# 08_SAMA7G54-PMIC.net
KiCad netlist of a schematic drawn in Altium Designer
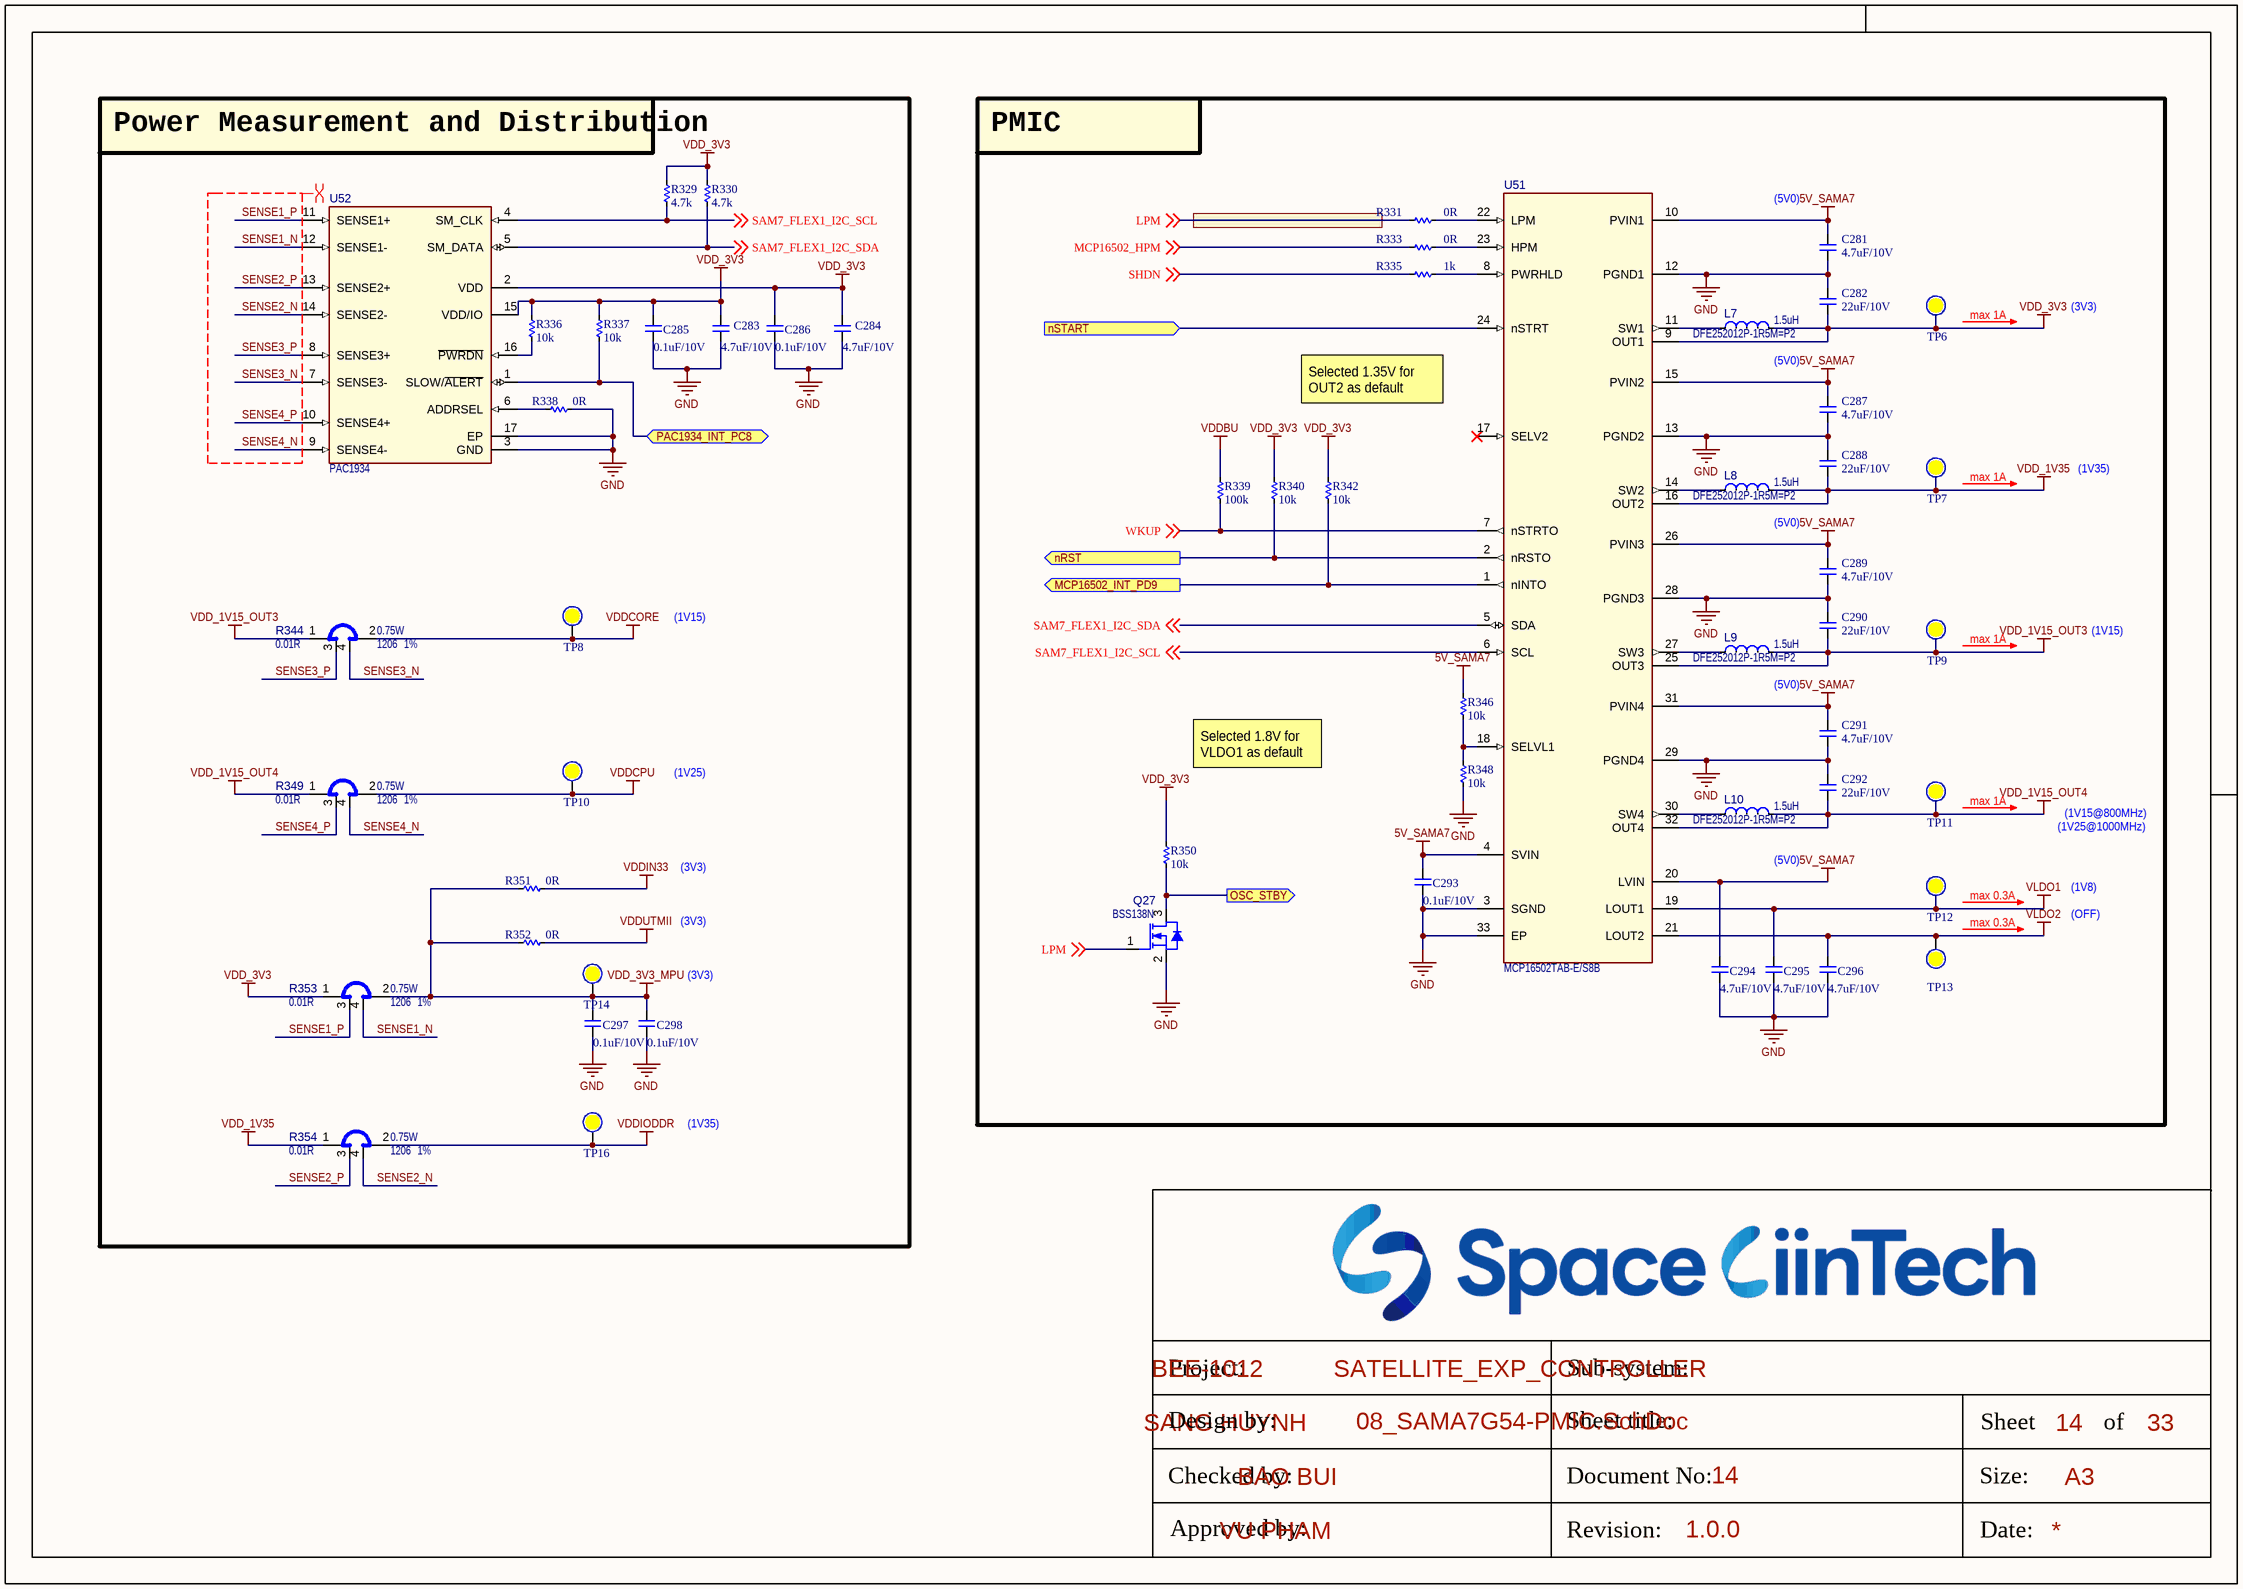
[diagram p0: 08_SAMA7G54-PMIC.SchDoc]

(export (version "E")
  (design (tool "Eeschema 10.0.6"))
  (components
    (comp (ref "C281")
      (value "4.7uF/10V")
      (footprint "CAP_C_1005X50_L")
      (description "CAP")
      (libsource (lib "LABLIB") (part "_CAP_C_2"))
    )
    (comp (ref "C282")
      (value "22uF/10V")
      (footprint "CAP_C_1608X80")
      (description "CAP")
      (libsource (lib "LABLIB") (part "_CAP_C_2"))
    )
    (comp (ref "C283")
      (value "4.7uF/10V")
      (footprint "CAP_C_1005X50_L")
      (description "CAP")
      (libsource (lib "LABLIB") (part "_CAP_C_2"))
    )
    (comp (ref "C284")
      (value "4.7uF/10V")
      (footprint "CAP_C_1005X50_L")
      (description "CAP")
      (libsource (lib "LABLIB") (part "_CAP_C_2"))
    )
    (comp (ref "C285")
      (value "0.1uF/10V")
      (footprint "CAP_C_1005X50_L")
      (description "CAP")
      (libsource (lib "LABLIB") (part "_CAP_C_2"))
    )
    (comp (ref "C286")
      (value "0.1uF/10V")
      (footprint "CAP_C_0603x30")
      (description "CAP")
      (libsource (lib "LABLIB") (part "_CAP_C_2"))
    )
    (comp (ref "C287")
      (value "4.7uF/10V")
      (footprint "CAP_C_1005X50_L")
      (description "CAP")
      (libsource (lib "LABLIB") (part "_CAP_C_2"))
    )
    (comp (ref "C288")
      (value "22uF/10V")
      (footprint "CAP_C_1608X80")
      (description "CAP")
      (libsource (lib "LABLIB") (part "_CAP_C_2"))
    )
    (comp (ref "C289")
      (value "4.7uF/10V")
      (footprint "CAP_C_1005X50_L")
      (description "CAP")
      (libsource (lib "LABLIB") (part "_CAP_C_2"))
    )
    (comp (ref "C290")
      (value "22uF/10V")
      (footprint "CAP_C_1608X80")
      (description "CAP")
      (libsource (lib "LABLIB") (part "_CAP_C_2"))
    )
    (comp (ref "C291")
      (value "4.7uF/10V")
      (footprint "CAP_C_1005X50_L")
      (description "CAP")
      (libsource (lib "LABLIB") (part "_CAP_C_2"))
    )
    (comp (ref "C292")
      (value "22uF/10V")
      (footprint "CAP_C_1608X80")
      (description "CAP")
      (libsource (lib "LABLIB") (part "_CAP_C_2"))
    )
    (comp (ref "C293")
      (value "0.1uF/10V")
      (footprint "CAP_C_0603x30")
      (description "CAP")
      (libsource (lib "LABLIB") (part "_CAP_C_2"))
    )
    (comp (ref "C294")
      (value "4.7uF/10V")
      (footprint "CAP_C_1005X50_L")
      (description "CAP")
      (libsource (lib "LABLIB") (part "_CAP_C_2"))
    )
    (comp (ref "C295")
      (value "4.7uF/10V")
      (footprint "CAP_C_1005X50_L")
      (description "CAP")
      (libsource (lib "LABLIB") (part "_CAP_C_2"))
    )
    (comp (ref "C296")
      (value "4.7uF/10V")
      (footprint "CAP_C_1005X50_L")
      (description "CAP")
      (libsource (lib "LABLIB") (part "_CAP_C_2"))
    )
    (comp (ref "C297")
      (value "0.1uF/10V")
      (footprint "CAP_C_0603x30")
      (description "CAP")
      (libsource (lib "LABLIB") (part "_CAP_C_2"))
    )
    (comp (ref "C298")
      (value "0.1uF/10V")
      (footprint "CAP_C_0603x30")
      (description "CAP")
      (libsource (lib "LABLIB") (part "_CAP_C_2"))
    )
    (comp (ref "L7")
      (value "1.5uH")
      (footprint "IND_C_1008")
      (description "Inductor")
      (fields
        (field (name "MANUFACTURER PART NUMBER 1") "DFE252012P-1R5M=P2")
        (field (name "Comment") "DFE252012P-1R5M=P2")
        (field (name "OWNER") "Razvan Cristescu")
      )
      (libsource (lib "LABLIB") (part "Inductor"))
    )
    (comp (ref "L8")
      (value "1.5uH")
      (footprint "IND_C_1008")
      (description "Inductor")
      (fields
        (field (name "MANUFACTURER PART NUMBER 1") "DFE252012P-1R5M=P2")
        (field (name "Comment") "DFE252012P-1R5M=P2")
        (field (name "OWNER") "Razvan Cristescu")
      )
      (libsource (lib "LABLIB") (part "Inductor"))
    )
    (comp (ref "L9")
      (value "1.5uH")
      (footprint "IND_C_1008")
      (description "Inductor")
      (fields
        (field (name "MANUFACTURER PART NUMBER 1") "DFE252012P-1R5M=P2")
        (field (name "Comment") "DFE252012P-1R5M=P2")
        (field (name "OWNER") "Razvan Cristescu")
      )
      (libsource (lib "LABLIB") (part "Inductor"))
    )
    (comp (ref "L10")
      (value "1.5uH")
      (footprint "IND_C_1008")
      (description "Inductor")
      (fields
        (field (name "MANUFACTURER PART NUMBER 1") "DFE252012P-1R5M=P2")
        (field (name "Comment") "DFE252012P-1R5M=P2")
        (field (name "OWNER") "Razvan Cristescu")
      )
      (libsource (lib "LABLIB") (part "Inductor"))
    )
    (comp (ref "Q27")
      (value "BSS138N")
      (footprint "SOT-23-3")
      (description "Transistor MOS")
      (fields
        (field (name "POWER") "0.36W")
        (field (name "VOLTAGE") "60V")
        (field (name "OWNER") "Dragos Danaila")
      )
      (libsource (lib "LABLIB") (part "Transistor MOS-N GSD"))
    )
    (comp (ref "R329")
      (value "4.7k")
      (footprint "RES_C_1005x30_L")
      (description "RES")
      (libsource (lib "LABLIB") (part "_RES_B_2"))
    )
    (comp (ref "R330")
      (value "4.7k")
      (footprint "RES_C_1005x30_L")
      (description "RES")
      (libsource (lib "LABLIB") (part "_RES_B_2"))
    )
    (comp (ref "R331")
      (value "0R")
      (footprint "RES_C_0603X30")
      (description "RES")
      (libsource (lib "LABLIB") (part "_RES_B_2"))
    )
    (comp (ref "R333")
      (value "0R")
      (footprint "RES_C_0603X30")
      (description "RES")
      (libsource (lib "LABLIB") (part "_RES_B_2"))
    )
    (comp (ref "R335")
      (value "1k")
      (footprint "RES_C_0603X30")
      (description "RES")
      (libsource (lib "LABLIB") (part "_RES_B_2"))
    )
    (comp (ref "R336")
      (value "10k")
      (footprint "RES_C_1005x30_L")
      (description "RES")
      (libsource (lib "LABLIB") (part "_RES_B_2"))
    )
    (comp (ref "R337")
      (value "10k")
      (footprint "RES_C_1005x30_L")
      (description "RES")
      (libsource (lib "LABLIB") (part "_RES_B_2"))
    )
    (comp (ref "R338")
      (value "0R")
      (footprint "RES_C_0603X30")
      (description "RES")
      (libsource (lib "LABLIB") (part "_RES_B_2"))
    )
    (comp (ref "R339")
      (value "100k")
      (footprint "RES_C_0603X30")
      (description "RES")
      (libsource (lib "LABLIB") (part "_RES_B_2"))
    )
    (comp (ref "R340")
      (value "10k")
      (footprint "RES_C_0603X30")
      (description "RES")
      (libsource (lib "LABLIB") (part "_RES_B_2"))
    )
    (comp (ref "R342")
      (value "10k")
      (footprint "RES_C_0603X30")
      (description "RES")
      (libsource (lib "LABLIB") (part "_RES_B_2"))
    )
    (comp (ref "R344")
      (value "0.01R")
      (footprint "RES_C_1206_SHUNT")
      (description "Shunt")
      (fields
        (field (name "PACKAGE") "1206")
        (field (name "TOLERANCE") "1%")
        (field (name "POWER") "0.75W")
        (field (name "Comment") "KRL1632E-M-R010-F-T5")
        (field (name "OWNER") "Ciprian Abramov")
      )
      (libsource (lib "LABLIB") (part "Shunt 4 Pin"))
    )
    (comp (ref "R346")
      (value "10k")
      (footprint "RES_C_0603X30")
      (description "RES")
      (libsource (lib "LABLIB") (part "_RES_B_2"))
    )
    (comp (ref "R348")
      (value "10k")
      (footprint "RES_C_0603X30")
      (description "RES")
      (libsource (lib "LABLIB") (part "_RES_B_2"))
    )
    (comp (ref "R349")
      (value "0.01R")
      (footprint "RES_C_1206_SHUNT")
      (description "Shunt")
      (fields
        (field (name "PACKAGE") "1206")
        (field (name "TOLERANCE") "1%")
        (field (name "POWER") "0.75W")
        (field (name "Comment") "KRL1632E-M-R010-F-T5")
        (field (name "OWNER") "Ciprian Abramov")
      )
      (libsource (lib "LABLIB") (part "Shunt 4 Pin"))
    )
    (comp (ref "R350")
      (value "10k")
      (footprint "RES_C_0603X30")
      (description "RES")
      (libsource (lib "LABLIB") (part "_RES_B_2"))
    )
    (comp (ref "R351")
      (value "0R")
      (footprint "RES_C_1608X60_L")
      (description "RES")
      (libsource (lib "LABLIB") (part "_RES_B_2"))
    )
    (comp (ref "R352")
      (value "0R")
      (footprint "RES_C_1608X60_L")
      (description "RES")
      (libsource (lib "LABLIB") (part "_RES_B_2"))
    )
    (comp (ref "R353")
      (value "0.01R")
      (footprint "RES_C_1206_SHUNT")
      (description "Shunt")
      (fields
        (field (name "PACKAGE") "1206")
        (field (name "TOLERANCE") "1%")
        (field (name "POWER") "0.75W")
        (field (name "Comment") "KRL1632E-M-R010-F-T5")
        (field (name "OWNER") "Ciprian Abramov")
      )
      (libsource (lib "LABLIB") (part "Shunt 4 Pin"))
    )
    (comp (ref "R354")
      (value "0.01R")
      (footprint "RES_C_1206_SHUNT")
      (description "Shunt")
      (fields
        (field (name "PACKAGE") "1206")
        (field (name "TOLERANCE") "1%")
        (field (name "POWER") "0.75W")
        (field (name "Comment") "KRL1632E-M-R010-F-T5")
        (field (name "OWNER") "Ciprian Abramov")
      )
      (libsource (lib "LABLIB") (part "Shunt 4 Pin"))
    )
    (comp (ref "TP6")
      (value "~")
      (footprint "Testpoint_50")
      (description "Test Point")
      (libsource (lib "LABLIB") (part "Test Point"))
    )
    (comp (ref "TP7")
      (value "~")
      (footprint "Testpoint_50")
      (description "Test Point")
      (libsource (lib "LABLIB") (part "Test Point"))
    )
    (comp (ref "TP8")
      (value "~")
      (footprint "Testpoint_50")
      (description "Test Point")
      (libsource (lib "LABLIB") (part "Test Point"))
    )
    (comp (ref "TP9")
      (value "~")
      (footprint "Testpoint_50")
      (description "Test Point")
      (libsource (lib "LABLIB") (part "Test Point"))
    )
    (comp (ref "TP10")
      (value "~")
      (footprint "Testpoint_50")
      (description "Test Point")
      (libsource (lib "LABLIB") (part "Test Point"))
    )
    (comp (ref "TP11")
      (value "~")
      (footprint "Testpoint_50")
      (description "Test Point")
      (libsource (lib "LABLIB") (part "Test Point"))
    )
    (comp (ref "TP12")
      (value "~")
      (footprint "Testpoint_50")
      (description "Test Point")
      (libsource (lib "LABLIB") (part "Test Point"))
    )
    (comp (ref "TP13")
      (value "~")
      (footprint "Testpoint_50")
      (description "Test Point")
      (libsource (lib "") (part "Test Point_1"))
    )
    (comp (ref "TP14")
      (value "~")
      (footprint "Testpoint_50")
      (description "Test Point")
      (libsource (lib "LABLIB") (part "Test Point"))
    )
    (comp (ref "TP16")
      (value "~")
      (footprint "Testpoint_50")
      (description "Test Point")
      (libsource (lib "LABLIB") (part "Test Point"))
    )
    (comp (ref "U51")
      (value "MCP16502TAB-E/S8B")
      (footprint "QFN-32_5X5_EP3.7X3.7")
      (fields (field (name "Comment") "MCP16502 QFN-32") (field (name "OWNER") "Dragos Danaila"))
      (libsource (lib "LABLIB") (part "MCP16502 QFN-32"))
    )
    (comp (ref "U52")
      (value "PAC1934")
      (footprint "UQFN-16_4X4_EP2.6X2.6")
      (fields (field (name "Comment") "PAC1934 UQFN-16") (field (name "OWNER") "Ciprian Abramov"))
      (libsource (lib "LABLIB") (part "PAC1934 UQFN-16"))
    )
  )
  (nets
    (net (code "1") (name "/MCP16502_INT_PD9") (class "Default")
      (node (ref "R342") (pin "1") (pinfunction "1_1") (pintype "passive"))
      (node (ref "U51") (pin "1") (pinfunction "nINTO_1") (pintype "output"))
    )
    (net (code "2") (name "/OSC_STBY") (class "Default")
      (node (ref "Q27") (pin "3") (pinfunction "D_3") (pintype "passive"))
      (node (ref "R350") (pin "2") (pinfunction "2_2") (pintype "passive"))
    )
    (net (code "3") (name "/PAC1934_INT_PC8") (class "Default")
      (node (ref "R337") (pin "2") (pinfunction "2_2") (pintype "passive"))
      (node (ref "U52") (pin "1") (pinfunction "SLOW/~{ALERT}_1") (pintype "bidirectional"))
    )
    (net (code "4") (name "/SENSE1_N") (class "Default")
      (node (ref "R353") (pin "4") (pinfunction "4_4") (pintype "passive"))
      (node (ref "U52") (pin "12") (pinfunction "SENSE1-_12") (pintype "input"))
    )
    (net (code "5") (name "/SENSE1_P") (class "Default")
      (node (ref "R353") (pin "3") (pinfunction "3_3") (pintype "passive"))
      (node (ref "U52") (pin "11") (pinfunction "SENSE1+_11") (pintype "input"))
    )
    (net (code "6") (name "/SENSE2_N") (class "Default")
      (node (ref "R354") (pin "4") (pinfunction "4_4") (pintype "passive"))
      (node (ref "U52") (pin "14") (pinfunction "SENSE2-_14") (pintype "input"))
    )
    (net (code "7") (name "/SENSE2_P") (class "Default")
      (node (ref "R354") (pin "3") (pinfunction "3_3") (pintype "passive"))
      (node (ref "U52") (pin "13") (pinfunction "SENSE2+_13") (pintype "input"))
    )
    (net (code "8") (name "/SENSE3_N") (class "Default")
      (node (ref "R344") (pin "4") (pinfunction "4_4") (pintype "passive"))
      (node (ref "U52") (pin "7") (pinfunction "SENSE3-_7") (pintype "input"))
    )
    (net (code "9") (name "/SENSE3_P") (class "Default")
      (node (ref "R344") (pin "3") (pinfunction "3_3") (pintype "passive"))
      (node (ref "U52") (pin "8") (pinfunction "SENSE3+_8") (pintype "input"))
    )
    (net (code "10") (name "/SENSE4_N") (class "Default")
      (node (ref "R349") (pin "4") (pinfunction "4_4") (pintype "passive"))
      (node (ref "U52") (pin "9") (pinfunction "SENSE4-_9") (pintype "input"))
    )
    (net (code "11") (name "/SENSE4_P") (class "Default")
      (node (ref "R349") (pin "3") (pinfunction "3_3") (pintype "passive"))
      (node (ref "U52") (pin "10") (pinfunction "SENSE4+_10") (pintype "input"))
    )
    (net (code "12") (name "/nRST") (class "Default")
      (node (ref "R340") (pin "1") (pinfunction "1_1") (pintype "passive"))
      (node (ref "U51") (pin "2") (pinfunction "nRSTO_2") (pintype "output"))
    )
    (net (code "13") (name "/nSTART") (class "Default")
      (node (ref "U51") (pin "24") (pinfunction "nSTRT_24") (pintype "input"))
    )
    (net (code "14") (name "5V_SAMA7") (class "Default")
      (node (ref "C281") (pin "1") (pinfunction "1_1") (pintype "passive"))
      (node (ref "C287") (pin "1") (pinfunction "1_1") (pintype "passive"))
      (node (ref "C289") (pin "1") (pinfunction "1_1") (pintype "passive"))
      (node (ref "C291") (pin "1") (pinfunction "1_1") (pintype "passive"))
      (node (ref "C293") (pin "1") (pinfunction "1_1") (pintype "passive"))
      (node (ref "C294") (pin "1") (pinfunction "1_1") (pintype "passive"))
      (node (ref "R346") (pin "1") (pinfunction "1_1") (pintype "passive"))
      (node (ref "U51") (pin "10") (pinfunction "PVIN1_10") (pintype "power_in"))
      (node (ref "U51") (pin "15") (pinfunction "PVIN2_15") (pintype "power_in"))
      (node (ref "U51") (pin "20") (pinfunction "LVIN_20") (pintype "power_in"))
      (node (ref "U51") (pin "26") (pinfunction "PVIN3_26") (pintype "power_in"))
      (node (ref "U51") (pin "31") (pinfunction "PVIN4_31") (pintype "power_in"))
      (node (ref "U51") (pin "4") (pinfunction "SVIN_4") (pintype "power_in"))
    )
    (net (code "15") (name "GND") (class "Default")
      (node (ref "C281") (pin "2") (pinfunction "2_2") (pintype "passive"))
      (node (ref "C282") (pin "1") (pinfunction "1_1") (pintype "passive"))
      (node (ref "C283") (pin "2") (pinfunction "2_2") (pintype "passive"))
      (node (ref "C284") (pin "2") (pinfunction "2_2") (pintype "passive"))
      (node (ref "C285") (pin "2") (pinfunction "2_2") (pintype "passive"))
      (node (ref "C286") (pin "2") (pinfunction "2_2") (pintype "passive"))
      (node (ref "C287") (pin "2") (pinfunction "2_2") (pintype "passive"))
      (node (ref "C288") (pin "1") (pinfunction "1_1") (pintype "passive"))
      (node (ref "C289") (pin "2") (pinfunction "2_2") (pintype "passive"))
      (node (ref "C290") (pin "1") (pinfunction "1_1") (pintype "passive"))
      (node (ref "C291") (pin "2") (pinfunction "2_2") (pintype "passive"))
      (node (ref "C292") (pin "1") (pinfunction "1_1") (pintype "passive"))
      (node (ref "C293") (pin "2") (pinfunction "2_2") (pintype "passive"))
      (node (ref "C294") (pin "2") (pinfunction "2_2") (pintype "passive"))
      (node (ref "C295") (pin "2") (pinfunction "2_2") (pintype "passive"))
      (node (ref "C296") (pin "2") (pinfunction "2_2") (pintype "passive"))
      (node (ref "C297") (pin "2") (pinfunction "2_2") (pintype "passive"))
      (node (ref "C298") (pin "2") (pinfunction "2_2") (pintype "passive"))
      (node (ref "Q27") (pin "2") (pinfunction "S_2") (pintype "passive"))
      (node (ref "R338") (pin "2") (pinfunction "2_2") (pintype "passive"))
      (node (ref "R348") (pin "2") (pinfunction "2_2") (pintype "passive"))
      (node (ref "U51") (pin "12") (pinfunction "PGND1_12") (pintype "power_in"))
      (node (ref "U51") (pin "13") (pinfunction "PGND2_13") (pintype "power_in"))
      (node (ref "U51") (pin "28") (pinfunction "PGND3_28") (pintype "power_in"))
      (node (ref "U51") (pin "29") (pinfunction "PGND4_29") (pintype "power_in"))
      (node (ref "U51") (pin "3") (pinfunction "SGND_3") (pintype "power_in"))
      (node (ref "U51") (pin "33") (pinfunction "EP_33") (pintype "power_in"))
      (node (ref "U52") (pin "17") (pinfunction "EP_17") (pintype "passive"))
      (node (ref "U52") (pin "3") (pinfunction "GND_3") (pintype "power_in"))
    )
    (net (code "16") (name "LPM") (class "Default")
      (node (ref "Q27") (pin "1") (pinfunction "G_1") (pintype "passive"))
      (node (ref "R331") (pin "1") (pinfunction "1_1") (pintype "passive"))
    )
    (net (code "17") (name "MCP16502_HPM") (class "Default")
      (node (ref "R333") (pin "1") (pinfunction "1_1") (pintype "passive"))
    )
    (net (code "18") (name "Net-(L7-S)") (class "Default")
      (node (ref "L7") (pin "1") (pinfunction "S_1") (pintype "passive"))
      (node (ref "U51") (pin "11") (pinfunction "SW1_11") (pintype "output"))
    )
    (net (code "19") (name "Net-(L8-S)") (class "Default")
      (node (ref "L8") (pin "1") (pinfunction "S_1") (pintype "passive"))
      (node (ref "U51") (pin "14") (pinfunction "SW2_14") (pintype "output"))
    )
    (net (code "20") (name "Net-(L9-S)") (class "Default")
      (node (ref "L9") (pin "1") (pinfunction "S_1") (pintype "passive"))
      (node (ref "U51") (pin "27") (pinfunction "SW3_27") (pintype "output"))
    )
    (net (code "21") (name "Net-(L10-S)") (class "Default")
      (node (ref "L10") (pin "1") (pinfunction "S_1") (pintype "passive"))
      (node (ref "U51") (pin "30") (pinfunction "SW4_30") (pintype "output"))
    )
    (net (code "22") (name "Net-(U51-HPM)") (class "Default")
      (node (ref "R333") (pin "2") (pinfunction "2_2") (pintype "passive"))
      (node (ref "U51") (pin "23") (pinfunction "HPM_23") (pintype "input"))
    )
    (net (code "23") (name "Net-(U51-LPM)") (class "Default")
      (node (ref "R331") (pin "2") (pinfunction "2_2") (pintype "passive"))
      (node (ref "U51") (pin "22") (pinfunction "LPM_22") (pintype "input"))
    )
    (net (code "24") (name "Net-(U51-PWRHLD)") (class "Default")
      (node (ref "R335") (pin "2") (pinfunction "2_2") (pintype "passive"))
      (node (ref "U51") (pin "8") (pinfunction "PWRHLD_8") (pintype "input"))
    )
    (net (code "25") (name "Net-(U51-SELVL1)") (class "Default")
      (node (ref "R346") (pin "2") (pinfunction "2_2") (pintype "passive"))
      (node (ref "R348") (pin "1") (pinfunction "1_1") (pintype "passive"))
      (node (ref "U51") (pin "18") (pinfunction "SELVL1_18") (pintype "input"))
    )
    (net (code "26") (name "Net-(U52-ADDRSEL)") (class "Default")
      (node (ref "R338") (pin "1") (pinfunction "1_1") (pintype "passive"))
      (node (ref "U52") (pin "6") (pinfunction "ADDRSEL_6") (pintype "input"))
    )
    (net (code "27") (name "Net-(U52-~{PWRDN})") (class "Default")
      (node (ref "R336") (pin "2") (pinfunction "2_2") (pintype "passive"))
      (node (ref "U52") (pin "16") (pinfunction "~{PWRDN}_16") (pintype "input"))
    )
    (net (code "28") (name "SAM7_FLEX1_I2C_SCL") (class "Default")
      (node (ref "R329") (pin "2") (pinfunction "2_2") (pintype "passive"))
      (node (ref "U51") (pin "6") (pinfunction "SCL_6") (pintype "input"))
      (node (ref "U52") (pin "4") (pinfunction "SM_CLK_4") (pintype "input"))
    )
    (net (code "29") (name "SAM7_FLEX1_I2C_SDA") (class "Default")
      (node (ref "R330") (pin "2") (pinfunction "2_2") (pintype "passive"))
      (node (ref "U51") (pin "5") (pinfunction "SDA_5") (pintype "bidirectional"))
      (node (ref "U52") (pin "5") (pinfunction "SM_DATA_5") (pintype "bidirectional"))
    )
    (net (code "30") (name "SHDN") (class "Default")
      (node (ref "R335") (pin "1") (pinfunction "1_1") (pintype "passive"))
    )
    (net (code "31") (name "VDDBU") (class "Default")
      (node (ref "R339") (pin "2") (pinfunction "2_2") (pintype "passive"))
    )
    (net (code "32") (name "VDDCORE") (class "Default")
      (node (ref "R344") (pin "2") (pinfunction "2_2") (pintype "passive"))
      (node (ref "TP8") (pin "0") (pinfunction "0_0") (pintype "passive"))
    )
    (net (code "33") (name "VDDCPU") (class "Default")
      (node (ref "R349") (pin "2") (pinfunction "2_2") (pintype "passive"))
      (node (ref "TP10") (pin "0") (pinfunction "0_0") (pintype "passive"))
    )
    (net (code "34") (name "VDDIN33") (class "Default")
      (node (ref "R351") (pin "2") (pinfunction "2_2") (pintype "passive"))
    )
    (net (code "35") (name "VDDIODDR") (class "Default")
      (node (ref "R354") (pin "2") (pinfunction "2_2") (pintype "passive"))
      (node (ref "TP16") (pin "0") (pinfunction "0_0") (pintype "passive"))
    )
    (net (code "36") (name "VDDUTMII") (class "Default")
      (node (ref "R352") (pin "2") (pinfunction "2_2") (pintype "passive"))
    )
    (net (code "37") (name "VDD_1V15_OUT3") (class "Default")
      (node (ref "C290") (pin "2") (pinfunction "2_2") (pintype "passive"))
      (node (ref "L9") (pin "2") (pinfunction "F_2") (pintype "passive"))
      (node (ref "R344") (pin "1") (pinfunction "1_1") (pintype "passive"))
      (node (ref "TP9") (pin "0") (pinfunction "0_0") (pintype "passive"))
      (node (ref "U51") (pin "25") (pinfunction "OUT3_25") (pintype "power_in"))
    )
    (net (code "38") (name "VDD_1V15_OUT4") (class "Default")
      (node (ref "C292") (pin "2") (pinfunction "2_2") (pintype "passive"))
      (node (ref "L10") (pin "2") (pinfunction "F_2") (pintype "passive"))
      (node (ref "R349") (pin "1") (pinfunction "1_1") (pintype "passive"))
      (node (ref "TP11") (pin "0") (pinfunction "0_0") (pintype "passive"))
      (node (ref "U51") (pin "32") (pinfunction "OUT4_32") (pintype "power_in"))
    )
    (net (code "39") (name "VDD_1V35") (class "Default")
      (node (ref "C288") (pin "2") (pinfunction "2_2") (pintype "passive"))
      (node (ref "L8") (pin "2") (pinfunction "F_2") (pintype "passive"))
      (node (ref "R354") (pin "1") (pinfunction "1_1") (pintype "passive"))
      (node (ref "TP7") (pin "0") (pinfunction "0_0") (pintype "passive"))
      (node (ref "U51") (pin "16") (pinfunction "OUT2_16") (pintype "power_in"))
    )
    (net (code "40") (name "VDD_3V3") (class "Default")
      (node (ref "C282") (pin "2") (pinfunction "2_2") (pintype "passive"))
      (node (ref "C283") (pin "1") (pinfunction "1_1") (pintype "passive"))
      (node (ref "C284") (pin "1") (pinfunction "1_1") (pintype "passive"))
      (node (ref "C285") (pin "1") (pinfunction "1_1") (pintype "passive"))
      (node (ref "C286") (pin "1") (pinfunction "1_1") (pintype "passive"))
      (node (ref "L7") (pin "2") (pinfunction "F_2") (pintype "passive"))
      (node (ref "R329") (pin "1") (pinfunction "1_1") (pintype "passive"))
      (node (ref "R330") (pin "1") (pinfunction "1_1") (pintype "passive"))
      (node (ref "R336") (pin "1") (pinfunction "1_1") (pintype "passive"))
      (node (ref "R337") (pin "1") (pinfunction "1_1") (pintype "passive"))
      (node (ref "R340") (pin "2") (pinfunction "2_2") (pintype "passive"))
      (node (ref "R342") (pin "2") (pinfunction "2_2") (pintype "passive"))
      (node (ref "R350") (pin "1") (pinfunction "1_1") (pintype "passive"))
      (node (ref "R353") (pin "1") (pinfunction "1_1") (pintype "passive"))
      (node (ref "TP6") (pin "0") (pinfunction "0_0") (pintype "passive"))
      (node (ref "U51") (pin "9") (pinfunction "OUT1_9") (pintype "power_in"))
      (node (ref "U52") (pin "15") (pinfunction "VDD/IO_15") (pintype "power_in"))
      (node (ref "U52") (pin "2") (pinfunction "VDD_2") (pintype "power_in"))
    )
    (net (code "41") (name "VDD_3V3_MPU") (class "Default")
      (node (ref "C297") (pin "1") (pinfunction "1_1") (pintype "passive"))
      (node (ref "C298") (pin "1") (pinfunction "1_1") (pintype "passive"))
      (node (ref "R351") (pin "1") (pinfunction "1_1") (pintype "passive"))
      (node (ref "R352") (pin "1") (pinfunction "1_1") (pintype "passive"))
      (node (ref "R353") (pin "2") (pinfunction "2_2") (pintype "passive"))
      (node (ref "TP14") (pin "0") (pinfunction "0_0") (pintype "passive"))
    )
    (net (code "42") (name "VLDO1") (class "Default")
      (node (ref "C295") (pin "1") (pinfunction "1_1") (pintype "passive"))
      (node (ref "TP12") (pin "0") (pinfunction "0_0") (pintype "passive"))
      (node (ref "U51") (pin "19") (pinfunction "LOUT1_19") (pintype "power_in"))
    )
    (net (code "43") (name "VLDO2") (class "Default")
      (node (ref "C296") (pin "1") (pinfunction "1_1") (pintype "passive"))
      (node (ref "TP13") (pin "0") (pinfunction "0_0") (pintype "passive"))
      (node (ref "U51") (pin "21") (pinfunction "LOUT2_21") (pintype "power_in"))
    )
    (net (code "44") (name "WKUP") (class "Default")
      (node (ref "R339") (pin "1") (pinfunction "1_1") (pintype "passive"))
      (node (ref "U51") (pin "7") (pinfunction "nSTRTO_7") (pintype "output"))
    )
    (net (code "45") (name "unconnected-(U51-SELV2-Pad17)") (class "Default")
      (node (ref "U51") (pin "17") (pinfunction "SELV2_17") (pintype "input+no_connect"))
    )
  )
)
